# venti_ver2_0.net
KiCad netlist of a schematic drawn in EAGLE
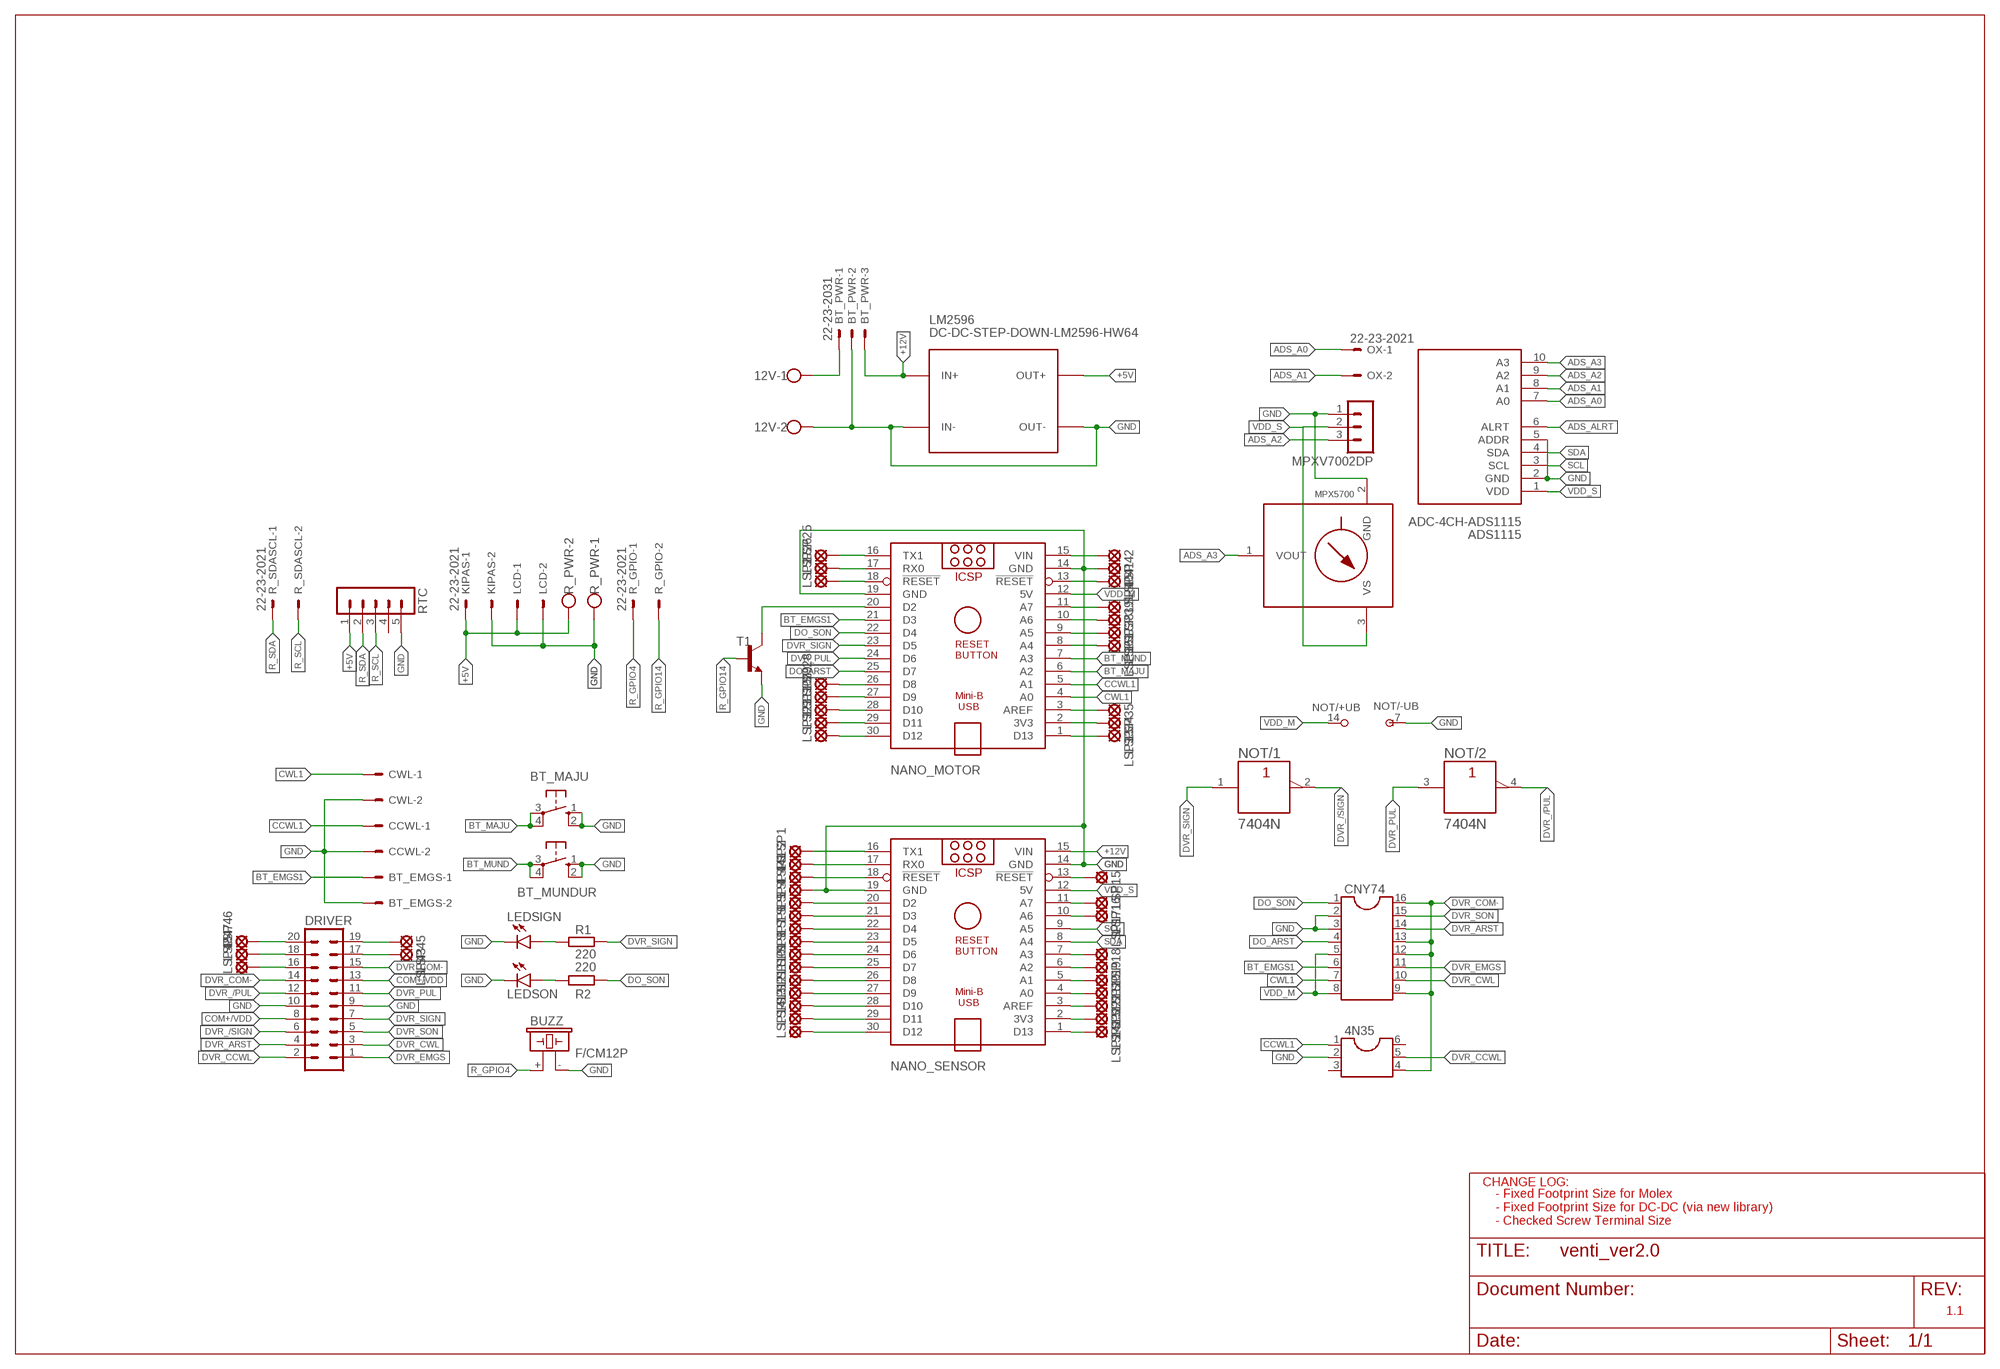
[diagram p0: schematic, sheet 1]

(export (version "E")
  (design (tool "Eeschema 10.0.6"))
  (components
    (comp (ref "4N35")
      (value "DIL6")
      (footprint "eagle-import:DIL06")
      (libsource (lib "eagle-import") (part "DIL6"))
    )
    (comp (ref "12V")
      (value "W237-102")
      (footprint "eagle-import:W237-102")
      (fields (field (name "MPN") "237-102"))
      (libsource (lib "eagle-import") (part "W237-102"))
    )
    (comp (ref "ADS1115")
      (value "ADC-4CH-ADS1115")
      (footprint "eagle-import:ADC-4CH-ADS1115")
      (libsource (lib "eagle-import") (part "ADC-4CH-ADS1115"))
    )
    (comp (ref "BT_EMGS")
      (value "22-23-2021")
      (footprint "eagle-import:22-23-2021")
      (fields (field (name "MF") "MOLEX"))
      (libsource (lib "eagle-import") (part "22-23-2021"))
    )
    (comp (ref "BT_MAJU")
      (value "40-XX")
      (footprint "eagle-import:B3F-40XX")
      (fields (field (name "MF") "OMRON COMPONENTS USA") (field (name "MPN") "B3F-4000"))
      (libsource (lib "eagle-import") (part "40-XX"))
    )
    (comp (ref "BT_MUNDUR")
      (value "40-XX")
      (footprint "eagle-import:B3F-40XX")
      (fields (field (name "MF") "OMRON COMPONENTS USA") (field (name "MPN") "B3F-4000"))
      (libsource (lib "eagle-import") (part "40-XX"))
    )
    (comp (ref "BT_PWR")
      (value "22-23-2031")
      (footprint "eagle-import:22-23-2031")
      (fields (field (name "MF") "MOLEX"))
      (libsource (lib "eagle-import") (part "22-23-2031"))
    )
    (comp (ref "BUZZ")
      (value "F/CM12P")
      (footprint "eagle-import:F_CM12P")
      (libsource (lib "eagle-import") (part "F/CM12P"))
    )
    (comp (ref "CCWL")
      (value "22-23-2021")
      (footprint "eagle-import:22-23-2021")
      (fields (field (name "MF") "MOLEX"))
      (libsource (lib "eagle-import") (part "22-23-2021"))
    )
    (comp (ref "CNY74")
      (value "DIL16")
      (footprint "eagle-import:DIL16")
      (libsource (lib "eagle-import") (part "DIL16"))
    )
    (comp (ref "CWL")
      (value "22-23-2021")
      (footprint "eagle-import:22-23-2021")
      (fields (field (name "MF") "MOLEX"))
      (libsource (lib "eagle-import") (part "22-23-2021"))
    )
    (comp (ref "DRIVER")
      (value "ML20")
      (footprint "eagle-import:ML20")
      (libsource (lib "eagle-import") (part "ML20"))
    )
    (comp (ref "KIPAS")
      (value "22-23-2021")
      (footprint "eagle-import:22-23-2021")
      (fields (field (name "MF") "MOLEX"))
      (libsource (lib "eagle-import") (part "22-23-2021"))
    )
    (comp (ref "LCD")
      (value "22-23-2021")
      (footprint "eagle-import:22-23-2021")
      (fields (field (name "MF") "MOLEX"))
      (libsource (lib "eagle-import") (part "22-23-2021"))
    )
    (comp (ref "LEDSIGN")
      (value "LED5MM")
      (footprint "eagle-import:LED5MM")
      (libsource (lib "eagle-import") (part "LED5MM"))
    )
    (comp (ref "LEDSON")
      (value "LED5MM")
      (footprint "eagle-import:LED5MM")
      (libsource (lib "eagle-import") (part "LED5MM"))
    )
    (comp (ref "LM2596")
      (value "DC-DC-STEP-DOWN-LM2596-HW64")
      (footprint "eagle-import:DC-DC-STEP-DOWN-LM2596")
      (libsource (lib "eagle-import") (part "DC-DC-STEP-DOWN-LM2596-HW64"))
    )
    (comp (ref "LSP1")
      (value "LSP11")
      (footprint "eagle-import:LSP11")
      (libsource (lib "eagle-import") (part "LSP11"))
    )
    (comp (ref "LSP2")
      (value "LSP11")
      (footprint "eagle-import:LSP11")
      (libsource (lib "eagle-import") (part "LSP11"))
    )
    (comp (ref "LSP3")
      (value "LSP11")
      (footprint "eagle-import:LSP11")
      (libsource (lib "eagle-import") (part "LSP11"))
    )
    (comp (ref "LSP4")
      (value "LSP11")
      (footprint "eagle-import:LSP11")
      (libsource (lib "eagle-import") (part "LSP11"))
    )
    (comp (ref "LSP5")
      (value "LSP11")
      (footprint "eagle-import:LSP11")
      (libsource (lib "eagle-import") (part "LSP11"))
    )
    (comp (ref "LSP6")
      (value "LSP11")
      (footprint "eagle-import:LSP11")
      (libsource (lib "eagle-import") (part "LSP11"))
    )
    (comp (ref "LSP7")
      (value "LSP11")
      (footprint "eagle-import:LSP11")
      (libsource (lib "eagle-import") (part "LSP11"))
    )
    (comp (ref "LSP8")
      (value "LSP11")
      (footprint "eagle-import:LSP11")
      (libsource (lib "eagle-import") (part "LSP11"))
    )
    (comp (ref "LSP9")
      (value "LSP11")
      (footprint "eagle-import:LSP11")
      (libsource (lib "eagle-import") (part "LSP11"))
    )
    (comp (ref "LSP10")
      (value "LSP11")
      (footprint "eagle-import:LSP11")
      (libsource (lib "eagle-import") (part "LSP11"))
    )
    (comp (ref "LSP11")
      (value "LSP11")
      (footprint "eagle-import:LSP11")
      (libsource (lib "eagle-import") (part "LSP11"))
    )
    (comp (ref "LSP12")
      (value "LSP11")
      (footprint "eagle-import:LSP11")
      (libsource (lib "eagle-import") (part "LSP11"))
    )
    (comp (ref "LSP13")
      (value "LSP11")
      (footprint "eagle-import:LSP11")
      (libsource (lib "eagle-import") (part "LSP11"))
    )
    (comp (ref "LSP14")
      (value "LSP11")
      (footprint "eagle-import:LSP11")
      (libsource (lib "eagle-import") (part "LSP11"))
    )
    (comp (ref "LSP15")
      (value "LSP11")
      (footprint "eagle-import:LSP11")
      (libsource (lib "eagle-import") (part "LSP11"))
    )
    (comp (ref "LSP16")
      (value "LSP11")
      (footprint "eagle-import:LSP11")
      (libsource (lib "eagle-import") (part "LSP11"))
    )
    (comp (ref "LSP17")
      (value "LSP11")
      (footprint "eagle-import:LSP11")
      (libsource (lib "eagle-import") (part "LSP11"))
    )
    (comp (ref "LSP18")
      (value "LSP11")
      (footprint "eagle-import:LSP11")
      (libsource (lib "eagle-import") (part "LSP11"))
    )
    (comp (ref "LSP19")
      (value "LSP11")
      (footprint "eagle-import:LSP11")
      (libsource (lib "eagle-import") (part "LSP11"))
    )
    (comp (ref "LSP20")
      (value "LSP11")
      (footprint "eagle-import:LSP11")
      (libsource (lib "eagle-import") (part "LSP11"))
    )
    (comp (ref "LSP21")
      (value "LSP11")
      (footprint "eagle-import:LSP11")
      (libsource (lib "eagle-import") (part "LSP11"))
    )
    (comp (ref "LSP22")
      (value "LSP11")
      (footprint "eagle-import:LSP11")
      (libsource (lib "eagle-import") (part "LSP11"))
    )
    (comp (ref "LSP23")
      (value "LSP11")
      (footprint "eagle-import:LSP11")
      (libsource (lib "eagle-import") (part "LSP11"))
    )
    (comp (ref "LSP24")
      (value "LSP11")
      (footprint "eagle-import:LSP11")
      (libsource (lib "eagle-import") (part "LSP11"))
    )
    (comp (ref "LSP25")
      (value "LSP11")
      (footprint "eagle-import:LSP11")
      (libsource (lib "eagle-import") (part "LSP11"))
    )
    (comp (ref "LSP26")
      (value "LSP11")
      (footprint "eagle-import:LSP11")
      (libsource (lib "eagle-import") (part "LSP11"))
    )
    (comp (ref "LSP27")
      (value "LSP11")
      (footprint "eagle-import:LSP11")
      (libsource (lib "eagle-import") (part "LSP11"))
    )
    (comp (ref "LSP28")
      (value "LSP11")
      (footprint "eagle-import:LSP11")
      (libsource (lib "eagle-import") (part "LSP11"))
    )
    (comp (ref "LSP29")
      (value "LSP11")
      (footprint "eagle-import:LSP11")
      (libsource (lib "eagle-import") (part "LSP11"))
    )
    (comp (ref "LSP30")
      (value "LSP11")
      (footprint "eagle-import:LSP11")
      (libsource (lib "eagle-import") (part "LSP11"))
    )
    (comp (ref "LSP31")
      (value "LSP11")
      (footprint "eagle-import:LSP11")
      (libsource (lib "eagle-import") (part "LSP11"))
    )
    (comp (ref "LSP32")
      (value "LSP11")
      (footprint "eagle-import:LSP11")
      (libsource (lib "eagle-import") (part "LSP11"))
    )
    (comp (ref "LSP33")
      (value "LSP11")
      (footprint "eagle-import:LSP11")
      (libsource (lib "eagle-import") (part "LSP11"))
    )
    (comp (ref "LSP34")
      (value "LSP11")
      (footprint "eagle-import:LSP11")
      (libsource (lib "eagle-import") (part "LSP11"))
    )
    (comp (ref "LSP35")
      (value "LSP11")
      (footprint "eagle-import:LSP11")
      (libsource (lib "eagle-import") (part "LSP11"))
    )
    (comp (ref "LSP36")
      (value "LSP11")
      (footprint "eagle-import:LSP11")
      (libsource (lib "eagle-import") (part "LSP11"))
    )
    (comp (ref "LSP37")
      (value "LSP11")
      (footprint "eagle-import:LSP11")
      (libsource (lib "eagle-import") (part "LSP11"))
    )
    (comp (ref "LSP38")
      (value "LSP11")
      (footprint "eagle-import:LSP11")
      (libsource (lib "eagle-import") (part "LSP11"))
    )
    (comp (ref "LSP39")
      (value "LSP11")
      (footprint "eagle-import:LSP11")
      (libsource (lib "eagle-import") (part "LSP11"))
    )
    (comp (ref "LSP40")
      (value "LSP11")
      (footprint "eagle-import:LSP11")
      (libsource (lib "eagle-import") (part "LSP11"))
    )
    (comp (ref "LSP41")
      (value "LSP11")
      (footprint "eagle-import:LSP11")
      (libsource (lib "eagle-import") (part "LSP11"))
    )
    (comp (ref "LSP42")
      (value "LSP11")
      (footprint "eagle-import:LSP11")
      (libsource (lib "eagle-import") (part "LSP11"))
    )
    (comp (ref "LSP43")
      (value "LSP11")
      (footprint "eagle-import:LSP11")
      (libsource (lib "eagle-import") (part "LSP11"))
    )
    (comp (ref "LSP44")
      (value "LSP11")
      (footprint "eagle-import:LSP11")
      (libsource (lib "eagle-import") (part "LSP11"))
    )
    (comp (ref "LSP45")
      (value "LSP11")
      (footprint "eagle-import:LSP11")
      (libsource (lib "eagle-import") (part "LSP11"))
    )
    (comp (ref "LSP46")
      (value "LSP11")
      (footprint "eagle-import:LSP11")
      (libsource (lib "eagle-import") (part "LSP11"))
    )
    (comp (ref "LSP47")
      (value "LSP11")
      (footprint "eagle-import:LSP11")
      (libsource (lib "eagle-import") (part "LSP11"))
    )
    (comp (ref "LSP48")
      (value "LSP11")
      (footprint "eagle-import:LSP11")
      (libsource (lib "eagle-import") (part "LSP11"))
    )
    (comp (ref "MPX5700")
      (value "MPX-867B-H")
      (footprint "eagle-import:867B-H")
      (libsource (lib "eagle-import") (part "MPX-867B-H"))
    )
    (comp (ref "MPXV7002DP")
      (value "MA03-1")
      (footprint "eagle-import:MA03-1")
      (libsource (lib "eagle-import") (part "MA03-1"))
    )
    (comp (ref "NANO_MOTOR")
      (value "ARDUINO_NANO")
      (footprint "eagle-import:ARDUINO_NANO")
      (libsource (lib "eagle-import") (part "ARDUINO_NANO"))
    )
    (comp (ref "NANO_SENSOR")
      (value "ARDUINO_NANO")
      (footprint "eagle-import:ARDUINO_NANO")
      (libsource (lib "eagle-import") (part "ARDUINO_NANO"))
    )
    (comp (ref "NOT")
      (value "7404N")
      (footprint "eagle-import:DIL14")
      (libsource (lib "eagle-import") (part "7404N"))
    )
    (comp (ref "OX")
      (value "22-23-2021")
      (footprint "eagle-import:22-23-2021")
      (fields (field (name "MF") "MOLEX"))
      (libsource (lib "eagle-import") (part "22-23-2021"))
    )
    (comp (ref "R1")
      (value "220")
      (footprint "eagle-import:0204_7")
      (libsource (lib "eagle-import") (part "R-EU_0204/7"))
    )
    (comp (ref "R2")
      (value "220")
      (footprint "eagle-import:0204_7")
      (libsource (lib "eagle-import") (part "R-EU_0204/7"))
    )
    (comp (ref "RTC")
      (value "MA05-1")
      (footprint "eagle-import:MA05-1")
      (libsource (lib "eagle-import") (part "MA05-1"))
    )
    (comp (ref "R_GPIO")
      (value "22-23-2021")
      (footprint "eagle-import:22-23-2021")
      (fields (field (name "MF") "MOLEX"))
      (libsource (lib "eagle-import") (part "22-23-2021"))
    )
    (comp (ref "R_PWR")
      (value "W237-102")
      (footprint "eagle-import:W237-102")
      (fields (field (name "MPN") "237-102"))
      (libsource (lib "eagle-import") (part "W237-102"))
    )
    (comp (ref "R_SDASCL")
      (value "22-23-2021")
      (footprint "eagle-import:22-23-2021")
      (fields (field (name "MF") "MOLEX"))
      (libsource (lib "eagle-import") (part "22-23-2021"))
    )
    (comp (ref "T1")
      (value "2N2222-NPN-TO92-EBC")
      (footprint "eagle-import:TO92-EBC")
      (libsource (lib "eagle-import") (part "-NPN-TO92-EBC2N2222"))
    )
  )
  (nets
    (net (code "1") (name "+5V") (class "Default")
      (node (ref "KIPAS") (pin "1") (pinfunction "S_1") (pintype "passive"))
      (node (ref "LCD") (pin "1") (pinfunction "S_1") (pintype "passive"))
      (node (ref "LM2596") (pin "OUT+") (pinfunction "OUT+_OUT+") (pintype "bidirectional"))
      (node (ref "RTC") (pin "1") (pinfunction "1_1") (pintype "passive"))
      (node (ref "R_PWR") (pin "2") (pinfunction "KL_2") (pintype "passive"))
    )
    (net (code "2") (name "+12V") (class "Default")
      (node (ref "BT_PWR") (pin "3") (pinfunction "S_3") (pintype "passive"))
      (node (ref "LM2596") (pin "IN+") (pinfunction "IN+_IN+") (pintype "bidirectional"))
      (node (ref "NANO_SENSOR") (pin "15") (pinfunction "VIN_15") (pintype "power_in"))
    )
    (net (code "3") (name "ADS_A0") (class "Default")
      (node (ref "ADS1115") (pin "7") (pinfunction "A0_7") (pintype "input"))
      (node (ref "OX") (pin "1") (pinfunction "S_1") (pintype "passive"))
    )
    (net (code "4") (name "ADS_A1") (class "Default")
      (node (ref "ADS1115") (pin "8") (pinfunction "A1_8") (pintype "input"))
      (node (ref "OX") (pin "2") (pinfunction "S_2") (pintype "passive"))
    )
    (net (code "5") (name "ADS_A2") (class "Default")
      (node (ref "ADS1115") (pin "9") (pinfunction "A2_9") (pintype "input"))
      (node (ref "MPXV7002DP") (pin "3") (pinfunction "3_3") (pintype "passive"))
    )
    (net (code "6") (name "ADS_A3") (class "Default")
      (node (ref "ADS1115") (pin "10") (pinfunction "A3_10") (pintype "input"))
      (node (ref "MPX5700") (pin "1") (pinfunction "VOUT_1") (pintype "output"))
    )
    (net (code "7") (name "ADS_ALRT") (class "Default")
      (node (ref "ADS1115") (pin "6") (pinfunction "ALRT_6") (pintype "bidirectional"))
    )
    (net (code "8") (name "BT_EMGS1") (class "Default")
      (node (ref "BT_EMGS") (pin "1") (pinfunction "S_1") (pintype "passive"))
      (node (ref "CNY74") (pin "6") (pinfunction "6_6") (pintype "passive"))
      (node (ref "NANO_MOTOR") (pin "21") (pinfunction "D3_21") (pintype "bidirectional"))
    )
    (net (code "9") (name "BT_MAJU") (class "Default")
      (node (ref "BT_MAJU") (pin "3") (pinfunction "P_3") (pintype "passive"))
      (node (ref "BT_MAJU") (pin "4") (pinfunction "P1_4") (pintype "passive"))
      (node (ref "NANO_MOTOR") (pin "6") (pinfunction "A2_6") (pintype "bidirectional"))
    )
    (net (code "10") (name "BT_MUND") (class "Default")
      (node (ref "BT_MUNDUR") (pin "3") (pinfunction "P_3") (pintype "passive"))
      (node (ref "BT_MUNDUR") (pin "4") (pinfunction "P1_4") (pintype "passive"))
      (node (ref "NANO_MOTOR") (pin "7") (pinfunction "A3_7") (pintype "bidirectional"))
    )
    (net (code "11") (name "CCWL1") (class "Default")
      (node (ref "4N35") (pin "1") (pinfunction "1_1") (pintype "passive"))
      (node (ref "CCWL") (pin "1") (pinfunction "S_1") (pintype "passive"))
      (node (ref "NANO_MOTOR") (pin "5") (pinfunction "A1_5") (pintype "bidirectional"))
    )
    (net (code "12") (name "COM+{slash}VDD") (class "Default")
      (node (ref "DRIVER") (pin "13") (pinfunction "13_13") (pintype "passive"))
      (node (ref "DRIVER") (pin "8") (pinfunction "8_8") (pintype "passive"))
    )
    (net (code "13") (name "CWL1") (class "Default")
      (node (ref "CNY74") (pin "7") (pinfunction "7_7") (pintype "passive"))
      (node (ref "CWL") (pin "1") (pinfunction "S_1") (pintype "passive"))
      (node (ref "NANO_MOTOR") (pin "4") (pinfunction "A0_4") (pintype "bidirectional"))
    )
    (net (code "14") (name "DO_ARST") (class "Default")
      (node (ref "CNY74") (pin "4") (pinfunction "4_4") (pintype "passive"))
      (node (ref "NANO_MOTOR") (pin "25") (pinfunction "D7_25") (pintype "bidirectional"))
    )
    (net (code "15") (name "DO_SON") (class "Default")
      (node (ref "CNY74") (pin "1") (pinfunction "1_1") (pintype "passive"))
      (node (ref "NANO_MOTOR") (pin "22") (pinfunction "D4_22") (pintype "bidirectional"))
      (node (ref "R2") (pin "2") (pinfunction "2_2") (pintype "passive"))
    )
    (net (code "16") (name "DVR_ARST") (class "Default")
      (node (ref "CNY74") (pin "14") (pinfunction "14_14") (pintype "passive"))
      (node (ref "DRIVER") (pin "4") (pinfunction "4_4") (pintype "passive"))
    )
    (net (code "17") (name "DVR_CCWL") (class "Default")
      (node (ref "4N35") (pin "5") (pinfunction "5_5") (pintype "passive"))
      (node (ref "DRIVER") (pin "2") (pinfunction "2_2") (pintype "passive"))
    )
    (net (code "18") (name "DVR_COM-") (class "Default")
      (node (ref "4N35") (pin "4") (pinfunction "4_4") (pintype "passive"))
      (node (ref "CNY74") (pin "12") (pinfunction "12_12") (pintype "passive"))
      (node (ref "CNY74") (pin "13") (pinfunction "13_13") (pintype "passive"))
      (node (ref "CNY74") (pin "16") (pinfunction "16_16") (pintype "passive"))
      (node (ref "CNY74") (pin "9") (pinfunction "9_9") (pintype "passive"))
      (node (ref "DRIVER") (pin "14") (pinfunction "14_14") (pintype "passive"))
      (node (ref "DRIVER") (pin "15") (pinfunction "15_15") (pintype "passive"))
    )
    (net (code "19") (name "DVR_CWL") (class "Default")
      (node (ref "CNY74") (pin "10") (pinfunction "10_10") (pintype "passive"))
      (node (ref "DRIVER") (pin "3") (pinfunction "3_3") (pintype "passive"))
    )
    (net (code "20") (name "DVR_EMGS") (class "Default")
      (node (ref "CNY74") (pin "11") (pinfunction "11_11") (pintype "passive"))
      (node (ref "DRIVER") (pin "1") (pinfunction "1_1") (pintype "passive"))
    )
    (net (code "21") (name "DVR_PUL") (class "Default")
      (node (ref "DRIVER") (pin "11") (pinfunction "11_11") (pintype "passive"))
      (node (ref "NANO_MOTOR") (pin "24") (pinfunction "D6_24") (pintype "bidirectional"))
      (node (ref "NOT") (pin "3") (pinfunction "A_3") (pintype "input"))
    )
    (net (code "22") (name "DVR_SIGN") (class "Default")
      (node (ref "DRIVER") (pin "7") (pinfunction "7_7") (pintype "passive"))
      (node (ref "NANO_MOTOR") (pin "23") (pinfunction "D5_23") (pintype "bidirectional"))
      (node (ref "NOT") (pin "1") (pinfunction "A_1") (pintype "input"))
      (node (ref "R1") (pin "2") (pinfunction "2_2") (pintype "passive"))
    )
    (net (code "23") (name "DVR_SON") (class "Default")
      (node (ref "CNY74") (pin "15") (pinfunction "15_15") (pintype "passive"))
      (node (ref "DRIVER") (pin "5") (pinfunction "5_5") (pintype "passive"))
    )
    (net (code "24") (name "DVR_{slash}PUL") (class "Default")
      (node (ref "DRIVER") (pin "12") (pinfunction "12_12") (pintype "passive"))
      (node (ref "NOT") (pin "4") (pinfunction "Y_4") (pintype "output"))
    )
    (net (code "25") (name "DVR_{slash}SIGN") (class "Default")
      (node (ref "DRIVER") (pin "6") (pinfunction "6_6") (pintype "passive"))
      (node (ref "NOT") (pin "2") (pinfunction "Y_2") (pintype "output"))
    )
    (net (code "26") (name "GND") (class "Default")
      (node (ref "12V") (pin "2") (pinfunction "KL_2") (pintype "passive"))
      (node (ref "4N35") (pin "2") (pinfunction "2_2") (pintype "passive"))
      (node (ref "ADS1115") (pin "2") (pinfunction "GND_2") (pintype "power_in"))
      (node (ref "ADS1115") (pin "5") (pinfunction "ADDR_5") (pintype "bidirectional"))
      (node (ref "BT_EMGS") (pin "2") (pinfunction "S_2") (pintype "passive"))
      (node (ref "BT_MAJU") (pin "1") (pinfunction "S_1") (pintype "passive"))
      (node (ref "BT_MAJU") (pin "2") (pinfunction "S1_2") (pintype "passive"))
      (node (ref "BT_MUNDUR") (pin "1") (pinfunction "S_1") (pintype "passive"))
      (node (ref "BT_MUNDUR") (pin "2") (pinfunction "S1_2") (pintype "passive"))
      (node (ref "BT_PWR") (pin "2") (pinfunction "S_2") (pintype "passive"))
      (node (ref "BUZZ") (pin "-") (pinfunction "2_-") (pintype "passive"))
      (node (ref "CCWL") (pin "2") (pinfunction "S_2") (pintype "passive"))
      (node (ref "CNY74") (pin "2") (pinfunction "2_2") (pintype "passive"))
      (node (ref "CNY74") (pin "3") (pinfunction "3_3") (pintype "passive"))
      (node (ref "CWL") (pin "2") (pinfunction "S_2") (pintype "passive"))
      (node (ref "DRIVER") (pin "10") (pinfunction "10_10") (pintype "passive"))
      (node (ref "DRIVER") (pin "9") (pinfunction "9_9") (pintype "passive"))
      (node (ref "KIPAS") (pin "2") (pinfunction "S_2") (pintype "passive"))
      (node (ref "LCD") (pin "2") (pinfunction "S_2") (pintype "passive"))
      (node (ref "LEDSIGN") (pin "K") (pinfunction "C_K") (pintype "passive"))
      (node (ref "LEDSON") (pin "K") (pinfunction "C_K") (pintype "passive"))
      (node (ref "LM2596") (pin "IN-") (pinfunction "IN-_IN-") (pintype "bidirectional"))
      (node (ref "LM2596") (pin "OUT-") (pinfunction "OUT-_OUT-") (pintype "bidirectional"))
      (node (ref "LSP41") (pin "MP") (pinfunction "MP_MP") (pintype "passive"))
      (node (ref "LSP44") (pin "MP") (pinfunction "MP_MP") (pintype "passive"))
      (node (ref "MPX5700") (pin "2") (pinfunction "GND_2") (pintype "power_in"))
      (node (ref "MPXV7002DP") (pin "1") (pinfunction "1_1") (pintype "passive"))
      (node (ref "NANO_MOTOR") (pin "14") (pinfunction "GND_14") (pintype "power_in"))
      (node (ref "NANO_MOTOR") (pin "19") (pinfunction "GND_19") (pintype "power_in"))
      (node (ref "NANO_SENSOR") (pin "14") (pinfunction "GND_14") (pintype "power_in"))
      (node (ref "NANO_SENSOR") (pin "19") (pinfunction "GND_19") (pintype "power_in"))
      (node (ref "NOT") (pin "7") (pinfunction "-UB_7") (pintype "power_in"))
      (node (ref "RTC") (pin "5") (pinfunction "5_5") (pintype "passive"))
      (node (ref "R_PWR") (pin "1") (pinfunction "KL_1") (pintype "passive"))
      (node (ref "T1") (pin "E") (pinfunction "E_E") (pintype "passive"))
    )
    (net (code "27") (name "Net-(12VA-KL)") (class "Default")
      (node (ref "12V") (pin "1") (pinfunction "KL_1") (pintype "passive"))
      (node (ref "BT_PWR") (pin "1") (pinfunction "S_1") (pintype "passive"))
    )
    (net (code "28") (name "Net-(DRIVER-Pad16)") (class "Default")
      (node (ref "DRIVER") (pin "16") (pinfunction "16_16") (pintype "passive"))
      (node (ref "LSP48") (pin "MP") (pinfunction "MP_MP") (pintype "passive"))
    )
    (net (code "29") (name "Net-(DRIVER-Pad17)") (class "Default")
      (node (ref "DRIVER") (pin "17") (pinfunction "17_17") (pintype "passive"))
      (node (ref "LSP43") (pin "MP") (pinfunction "MP_MP") (pintype "passive"))
    )
    (net (code "30") (name "Net-(DRIVER-Pad18)") (class "Default")
      (node (ref "DRIVER") (pin "18") (pinfunction "18_18") (pintype "passive"))
      (node (ref "LSP47") (pin "MP") (pinfunction "MP_MP") (pintype "passive"))
    )
    (net (code "31") (name "Net-(DRIVER-Pad19)") (class "Default")
      (node (ref "DRIVER") (pin "19") (pinfunction "19_19") (pintype "passive"))
      (node (ref "LSP45") (pin "MP") (pinfunction "MP_MP") (pintype "passive"))
    )
    (net (code "32") (name "Net-(DRIVER-Pad20)") (class "Default")
      (node (ref "DRIVER") (pin "20") (pinfunction "20_20") (pintype "passive"))
      (node (ref "LSP46") (pin "MP") (pinfunction "MP_MP") (pintype "passive"))
    )
    (net (code "33") (name "Net-(LEDSIGN-PadA)") (class "Default")
      (node (ref "LEDSIGN") (pin "A") (pinfunction "A_A") (pintype "passive"))
      (node (ref "R1") (pin "1") (pinfunction "1_1") (pintype "passive"))
    )
    (net (code "34") (name "Net-(LEDSON-PadA)") (class "Default")
      (node (ref "LEDSON") (pin "A") (pinfunction "A_A") (pintype "passive"))
      (node (ref "R2") (pin "1") (pinfunction "1_1") (pintype "passive"))
    )
    (net (code "35") (name "Net-(LSP3-PadMP)") (class "Default")
      (node (ref "LSP3") (pin "MP") (pinfunction "MP_MP") (pintype "passive"))
      (node (ref "NANO_SENSOR") (pin "18") (pinfunction "~{RESET}_18") (pintype "input"))
    )
    (net (code "36") (name "Net-(LSP15-PadMP)") (class "Default")
      (node (ref "LSP15") (pin "MP") (pinfunction "MP_MP") (pintype "passive"))
      (node (ref "NANO_SENSOR") (pin "13") (pinfunction "~{RESET}_13") (pintype "input"))
    )
    (net (code "37") (name "Net-(LSP27-PadMP)") (class "Default")
      (node (ref "LSP27") (pin "MP") (pinfunction "MP_MP") (pintype "passive"))
      (node (ref "NANO_MOTOR") (pin "18") (pinfunction "~{RESET}_18") (pintype "input"))
    )
    (net (code "38") (name "Net-(LSP40-PadMP)") (class "Default")
      (node (ref "LSP40") (pin "MP") (pinfunction "MP_MP") (pintype "passive"))
      (node (ref "NANO_MOTOR") (pin "13") (pinfunction "~{RESET}_13") (pintype "input"))
    )
    (net (code "39") (name "Net-(NANO_MOTOR-3V3)") (class "Default")
      (node (ref "LSP34") (pin "MP") (pinfunction "MP_MP") (pintype "passive"))
      (node (ref "NANO_MOTOR") (pin "2") (pinfunction "3V3_2") (pintype "output"))
    )
    (net (code "40") (name "Net-(NANO_MOTOR-A4)") (class "Default")
      (node (ref "LSP36") (pin "MP") (pinfunction "MP_MP") (pintype "passive"))
      (node (ref "NANO_MOTOR") (pin "8") (pinfunction "A4_8") (pintype "bidirectional"))
    )
    (net (code "41") (name "Net-(NANO_MOTOR-A5)") (class "Default")
      (node (ref "LSP37") (pin "MP") (pinfunction "MP_MP") (pintype "passive"))
      (node (ref "NANO_MOTOR") (pin "9") (pinfunction "A5_9") (pintype "bidirectional"))
    )
    (net (code "42") (name "Net-(NANO_MOTOR-A6)") (class "Default")
      (node (ref "LSP38") (pin "MP") (pinfunction "MP_MP") (pintype "passive"))
      (node (ref "NANO_MOTOR") (pin "10") (pinfunction "A6_10") (pintype "bidirectional"))
    )
    (net (code "43") (name "Net-(NANO_MOTOR-A7)") (class "Default")
      (node (ref "LSP39") (pin "MP") (pinfunction "MP_MP") (pintype "passive"))
      (node (ref "NANO_MOTOR") (pin "11") (pinfunction "A7_11") (pintype "bidirectional"))
    )
    (net (code "44") (name "Net-(NANO_MOTOR-AREF)") (class "Default")
      (node (ref "LSP35") (pin "MP") (pinfunction "MP_MP") (pintype "passive"))
      (node (ref "NANO_MOTOR") (pin "3") (pinfunction "AREF_3") (pintype "input"))
    )
    (net (code "45") (name "Net-(NANO_MOTOR-D2)") (class "Default")
      (node (ref "NANO_MOTOR") (pin "20") (pinfunction "D2_20") (pintype "bidirectional"))
      (node (ref "T1") (pin "C") (pinfunction "C_C") (pintype "passive"))
    )
    (net (code "46") (name "Net-(NANO_MOTOR-D8)") (class "Default")
      (node (ref "LSP28") (pin "MP") (pinfunction "MP_MP") (pintype "passive"))
      (node (ref "NANO_MOTOR") (pin "26") (pinfunction "D8_26") (pintype "bidirectional"))
    )
    (net (code "47") (name "Net-(NANO_MOTOR-D9)") (class "Default")
      (node (ref "LSP29") (pin "MP") (pinfunction "MP_MP") (pintype "passive"))
      (node (ref "NANO_MOTOR") (pin "27") (pinfunction "D9_27") (pintype "bidirectional"))
    )
    (net (code "48") (name "Net-(NANO_MOTOR-D10)") (class "Default")
      (node (ref "LSP30") (pin "MP") (pinfunction "MP_MP") (pintype "passive"))
      (node (ref "NANO_MOTOR") (pin "28") (pinfunction "D10_28") (pintype "bidirectional"))
    )
    (net (code "49") (name "Net-(NANO_MOTOR-D11)") (class "Default")
      (node (ref "LSP31") (pin "MP") (pinfunction "MP_MP") (pintype "passive"))
      (node (ref "NANO_MOTOR") (pin "29") (pinfunction "D11_29") (pintype "bidirectional"))
    )
    (net (code "50") (name "Net-(NANO_MOTOR-D12)") (class "Default")
      (node (ref "LSP32") (pin "MP") (pinfunction "MP_MP") (pintype "passive"))
      (node (ref "NANO_MOTOR") (pin "30") (pinfunction "D12_30") (pintype "bidirectional"))
    )
    (net (code "51") (name "Net-(NANO_MOTOR-D13)") (class "Default")
      (node (ref "LSP33") (pin "MP") (pinfunction "MP_MP") (pintype "passive"))
      (node (ref "NANO_MOTOR") (pin "1") (pinfunction "D13_1") (pintype "bidirectional"))
    )
    (net (code "52") (name "Net-(NANO_MOTOR-RX0)") (class "Default")
      (node (ref "LSP26") (pin "MP") (pinfunction "MP_MP") (pintype "passive"))
      (node (ref "NANO_MOTOR") (pin "17") (pinfunction "RX0_17") (pintype "bidirectional"))
    )
    (net (code "53") (name "Net-(NANO_MOTOR-TX1)") (class "Default")
      (node (ref "LSP25") (pin "MP") (pinfunction "MP_MP") (pintype "passive"))
      (node (ref "NANO_MOTOR") (pin "16") (pinfunction "TX1_16") (pintype "bidirectional"))
    )
    (net (code "54") (name "Net-(NANO_MOTOR-VIN)") (class "Default")
      (node (ref "LSP42") (pin "MP") (pinfunction "MP_MP") (pintype "passive"))
      (node (ref "NANO_MOTOR") (pin "15") (pinfunction "VIN_15") (pintype "power_in"))
    )
    (net (code "55") (name "Net-(NANO_SENSOR-3V3)") (class "Default")
      (node (ref "LSP23") (pin "MP") (pinfunction "MP_MP") (pintype "passive"))
      (node (ref "NANO_SENSOR") (pin "2") (pinfunction "3V3_2") (pintype "output"))
    )
    (net (code "56") (name "Net-(NANO_SENSOR-A0)") (class "Default")
      (node (ref "LSP21") (pin "MP") (pinfunction "MP_MP") (pintype "passive"))
      (node (ref "NANO_SENSOR") (pin "4") (pinfunction "A0_4") (pintype "bidirectional"))
    )
    (net (code "57") (name "Net-(NANO_SENSOR-A1)") (class "Default")
      (node (ref "LSP20") (pin "MP") (pinfunction "MP_MP") (pintype "passive"))
      (node (ref "NANO_SENSOR") (pin "5") (pinfunction "A1_5") (pintype "bidirectional"))
    )
    (net (code "58") (name "Net-(NANO_SENSOR-A2)") (class "Default")
      (node (ref "LSP19") (pin "MP") (pinfunction "MP_MP") (pintype "passive"))
      (node (ref "NANO_SENSOR") (pin "6") (pinfunction "A2_6") (pintype "bidirectional"))
    )
    (net (code "59") (name "Net-(NANO_SENSOR-A3)") (class "Default")
      (node (ref "LSP18") (pin "MP") (pinfunction "MP_MP") (pintype "passive"))
      (node (ref "NANO_SENSOR") (pin "7") (pinfunction "A3_7") (pintype "bidirectional"))
    )
    (net (code "60") (name "Net-(NANO_SENSOR-A6)") (class "Default")
      (node (ref "LSP17") (pin "MP") (pinfunction "MP_MP") (pintype "passive"))
      (node (ref "NANO_SENSOR") (pin "10") (pinfunction "A6_10") (pintype "bidirectional"))
    )
    (net (code "61") (name "Net-(NANO_SENSOR-A7)") (class "Default")
      (node (ref "LSP16") (pin "MP") (pinfunction "MP_MP") (pintype "passive"))
      (node (ref "NANO_SENSOR") (pin "11") (pinfunction "A7_11") (pintype "bidirectional"))
    )
    (net (code "62") (name "Net-(NANO_SENSOR-AREF)") (class "Default")
      (node (ref "LSP22") (pin "MP") (pinfunction "MP_MP") (pintype "passive"))
      (node (ref "NANO_SENSOR") (pin "3") (pinfunction "AREF_3") (pintype "input"))
    )
    (net (code "63") (name "Net-(NANO_SENSOR-D2)") (class "Default")
      (node (ref "LSP4") (pin "MP") (pinfunction "MP_MP") (pintype "passive"))
      (node (ref "NANO_SENSOR") (pin "20") (pinfunction "D2_20") (pintype "bidirectional"))
    )
    (net (code "64") (name "Net-(NANO_SENSOR-D3)") (class "Default")
      (node (ref "LSP5") (pin "MP") (pinfunction "MP_MP") (pintype "passive"))
      (node (ref "NANO_SENSOR") (pin "21") (pinfunction "D3_21") (pintype "bidirectional"))
    )
    (net (code "65") (name "Net-(NANO_SENSOR-D4)") (class "Default")
      (node (ref "LSP6") (pin "MP") (pinfunction "MP_MP") (pintype "passive"))
      (node (ref "NANO_SENSOR") (pin "22") (pinfunction "D4_22") (pintype "bidirectional"))
    )
    (net (code "66") (name "Net-(NANO_SENSOR-D5)") (class "Default")
      (node (ref "LSP7") (pin "MP") (pinfunction "MP_MP") (pintype "passive"))
      (node (ref "NANO_SENSOR") (pin "23") (pinfunction "D5_23") (pintype "bidirectional"))
    )
    (net (code "67") (name "Net-(NANO_SENSOR-D6)") (class "Default")
      (node (ref "LSP8") (pin "MP") (pinfunction "MP_MP") (pintype "passive"))
      (node (ref "NANO_SENSOR") (pin "24") (pinfunction "D6_24") (pintype "bidirectional"))
    )
    (net (code "68") (name "Net-(NANO_SENSOR-D7)") (class "Default")
      (node (ref "LSP9") (pin "MP") (pinfunction "MP_MP") (pintype "passive"))
      (node (ref "NANO_SENSOR") (pin "25") (pinfunction "D7_25") (pintype "bidirectional"))
    )
    (net (code "69") (name "Net-(NANO_SENSOR-D8)") (class "Default")
      (node (ref "LSP10") (pin "MP") (pinfunction "MP_MP") (pintype "passive"))
      (node (ref "NANO_SENSOR") (pin "26") (pinfunction "D8_26") (pintype "bidirectional"))
    )
    (net (code "70") (name "Net-(NANO_SENSOR-D9)") (class "Default")
      (node (ref "LSP11") (pin "MP") (pinfunction "MP_MP") (pintype "passive"))
      (node (ref "NANO_SENSOR") (pin "27") (pinfunction "D9_27") (pintype "bidirectional"))
    )
    (net (code "71") (name "Net-(NANO_SENSOR-D10)") (class "Default")
      (node (ref "LSP12") (pin "MP") (pinfunction "MP_MP") (pintype "passive"))
      (node (ref "NANO_SENSOR") (pin "28") (pinfunction "D10_28") (pintype "bidirectional"))
    )
    (net (code "72") (name "Net-(NANO_SENSOR-D11)") (class "Default")
      (node (ref "LSP13") (pin "MP") (pinfunction "MP_MP") (pintype "passive"))
      (node (ref "NANO_SENSOR") (pin "29") (pinfunction "D11_29") (pintype "bidirectional"))
    )
    (net (code "73") (name "Net-(NANO_SENSOR-D12)") (class "Default")
      (node (ref "LSP14") (pin "MP") (pinfunction "MP_MP") (pintype "passive"))
      (node (ref "NANO_SENSOR") (pin "30") (pinfunction "D12_30") (pintype "bidirectional"))
    )
    (net (code "74") (name "Net-(NANO_SENSOR-D13)") (class "Default")
      (node (ref "LSP24") (pin "MP") (pinfunction "MP_MP") (pintype "passive"))
      (node (ref "NANO_SENSOR") (pin "1") (pinfunction "D13_1") (pintype "bidirectional"))
    )
    (net (code "75") (name "Net-(NANO_SENSOR-RX0)") (class "Default")
      (node (ref "LSP2") (pin "MP") (pinfunction "MP_MP") (pintype "passive"))
      (node (ref "NANO_SENSOR") (pin "17") (pinfunction "RX0_17") (pintype "bidirectional"))
    )
    (net (code "76") (name "Net-(NANO_SENSOR-TX1)") (class "Default")
      (node (ref "LSP1") (pin "MP") (pinfunction "MP_MP") (pintype "passive"))
      (node (ref "NANO_SENSOR") (pin "16") (pinfunction "TX1_16") (pintype "bidirectional"))
    )
    (net (code "77") (name "R_GPIO4") (class "Default")
      (node (ref "BUZZ") (pin "+") (pinfunction "1_+") (pintype "passive"))
      (node (ref "R_GPIO") (pin "1") (pinfunction "S_1") (pintype "passive"))
    )
    (net (code "78") (name "R_GPIO14") (class "Default")
      (node (ref "R_GPIO") (pin "2") (pinfunction "S_2") (pintype "passive"))
      (node (ref "T1") (pin "B") (pinfunction "B_B") (pintype "passive"))
    )
    (net (code "79") (name "R_SCL") (class "Default")
      (node (ref "RTC") (pin "3") (pinfunction "3_3") (pintype "passive"))
      (node (ref "R_SDASCL") (pin "2") (pinfunction "S_2") (pintype "passive"))
    )
    (net (code "80") (name "R_SDA") (class "Default")
      (node (ref "RTC") (pin "2") (pinfunction "2_2") (pintype "passive"))
      (node (ref "R_SDASCL") (pin "1") (pinfunction "S_1") (pintype "passive"))
    )
    (net (code "81") (name "SCL") (class "Default")
      (node (ref "ADS1115") (pin "3") (pinfunction "SCL_3") (pintype "bidirectional"))
      (node (ref "NANO_SENSOR") (pin "9") (pinfunction "A5_9") (pintype "bidirectional"))
    )
    (net (code "82") (name "SDA") (class "Default")
      (node (ref "ADS1115") (pin "4") (pinfunction "SDA_4") (pintype "bidirectional"))
      (node (ref "NANO_SENSOR") (pin "8") (pinfunction "A4_8") (pintype "bidirectional"))
    )
    (net (code "83") (name "VDD_M") (class "Default")
      (node (ref "CNY74") (pin "5") (pinfunction "5_5") (pintype "passive"))
      (node (ref "CNY74") (pin "8") (pinfunction "8_8") (pintype "passive"))
      (node (ref "NANO_MOTOR") (pin "12") (pinfunction "5V_12") (pintype "power_in"))
      (node (ref "NOT") (pin "14") (pinfunction "+UB_14") (pintype "power_in"))
    )
    (net (code "84") (name "VDD_S") (class "Default")
      (node (ref "ADS1115") (pin "1") (pinfunction "VDD_1") (pintype "power_in"))
      (node (ref "MPX5700") (pin "3") (pinfunction "VS_3") (pintype "power_in"))
      (node (ref "MPXV7002DP") (pin "2") (pinfunction "2_2") (pintype "passive"))
      (node (ref "NANO_SENSOR") (pin "12") (pinfunction "5V_12") (pintype "power_in"))
    )
    (net (code "85") (name "unconnected-(4N35-Pad3)") (class "Default")
      (node (ref "4N35") (pin "3") (pinfunction "3_3") (pintype "passive"))
    )
    (net (code "86") (name "unconnected-(4N35-Pad6)") (class "Default")
      (node (ref "4N35") (pin "6") (pinfunction "6_6") (pintype "passive"))
    )
    (net (code "87") (name "unconnected-(MPX5700-NC-Pad4)") (class "Default")
      (node (ref "MPX5700") (pin "4") (pinfunction "NC_4") (pintype "no_connect"))
    )
    (net (code "88") (name "unconnected-(MPX5700-NC-Pad5)") (class "Default")
      (node (ref "MPX5700") (pin "5") (pinfunction "NC_5") (pintype "no_connect"))
    )
    (net (code "89") (name "unconnected-(MPX5700-NC-Pad6)") (class "Default")
      (node (ref "MPX5700") (pin "6") (pinfunction "NC_6") (pintype "no_connect"))
    )
    (net (code "90") (name "unconnected-(RTC-Pad4)") (class "Default")
      (node (ref "RTC") (pin "4") (pinfunction "4_4") (pintype "passive"))
    )
  )
)
